# Motor1_PCIe.net
KiCad netlist of a schematic drawn in Altium Designer
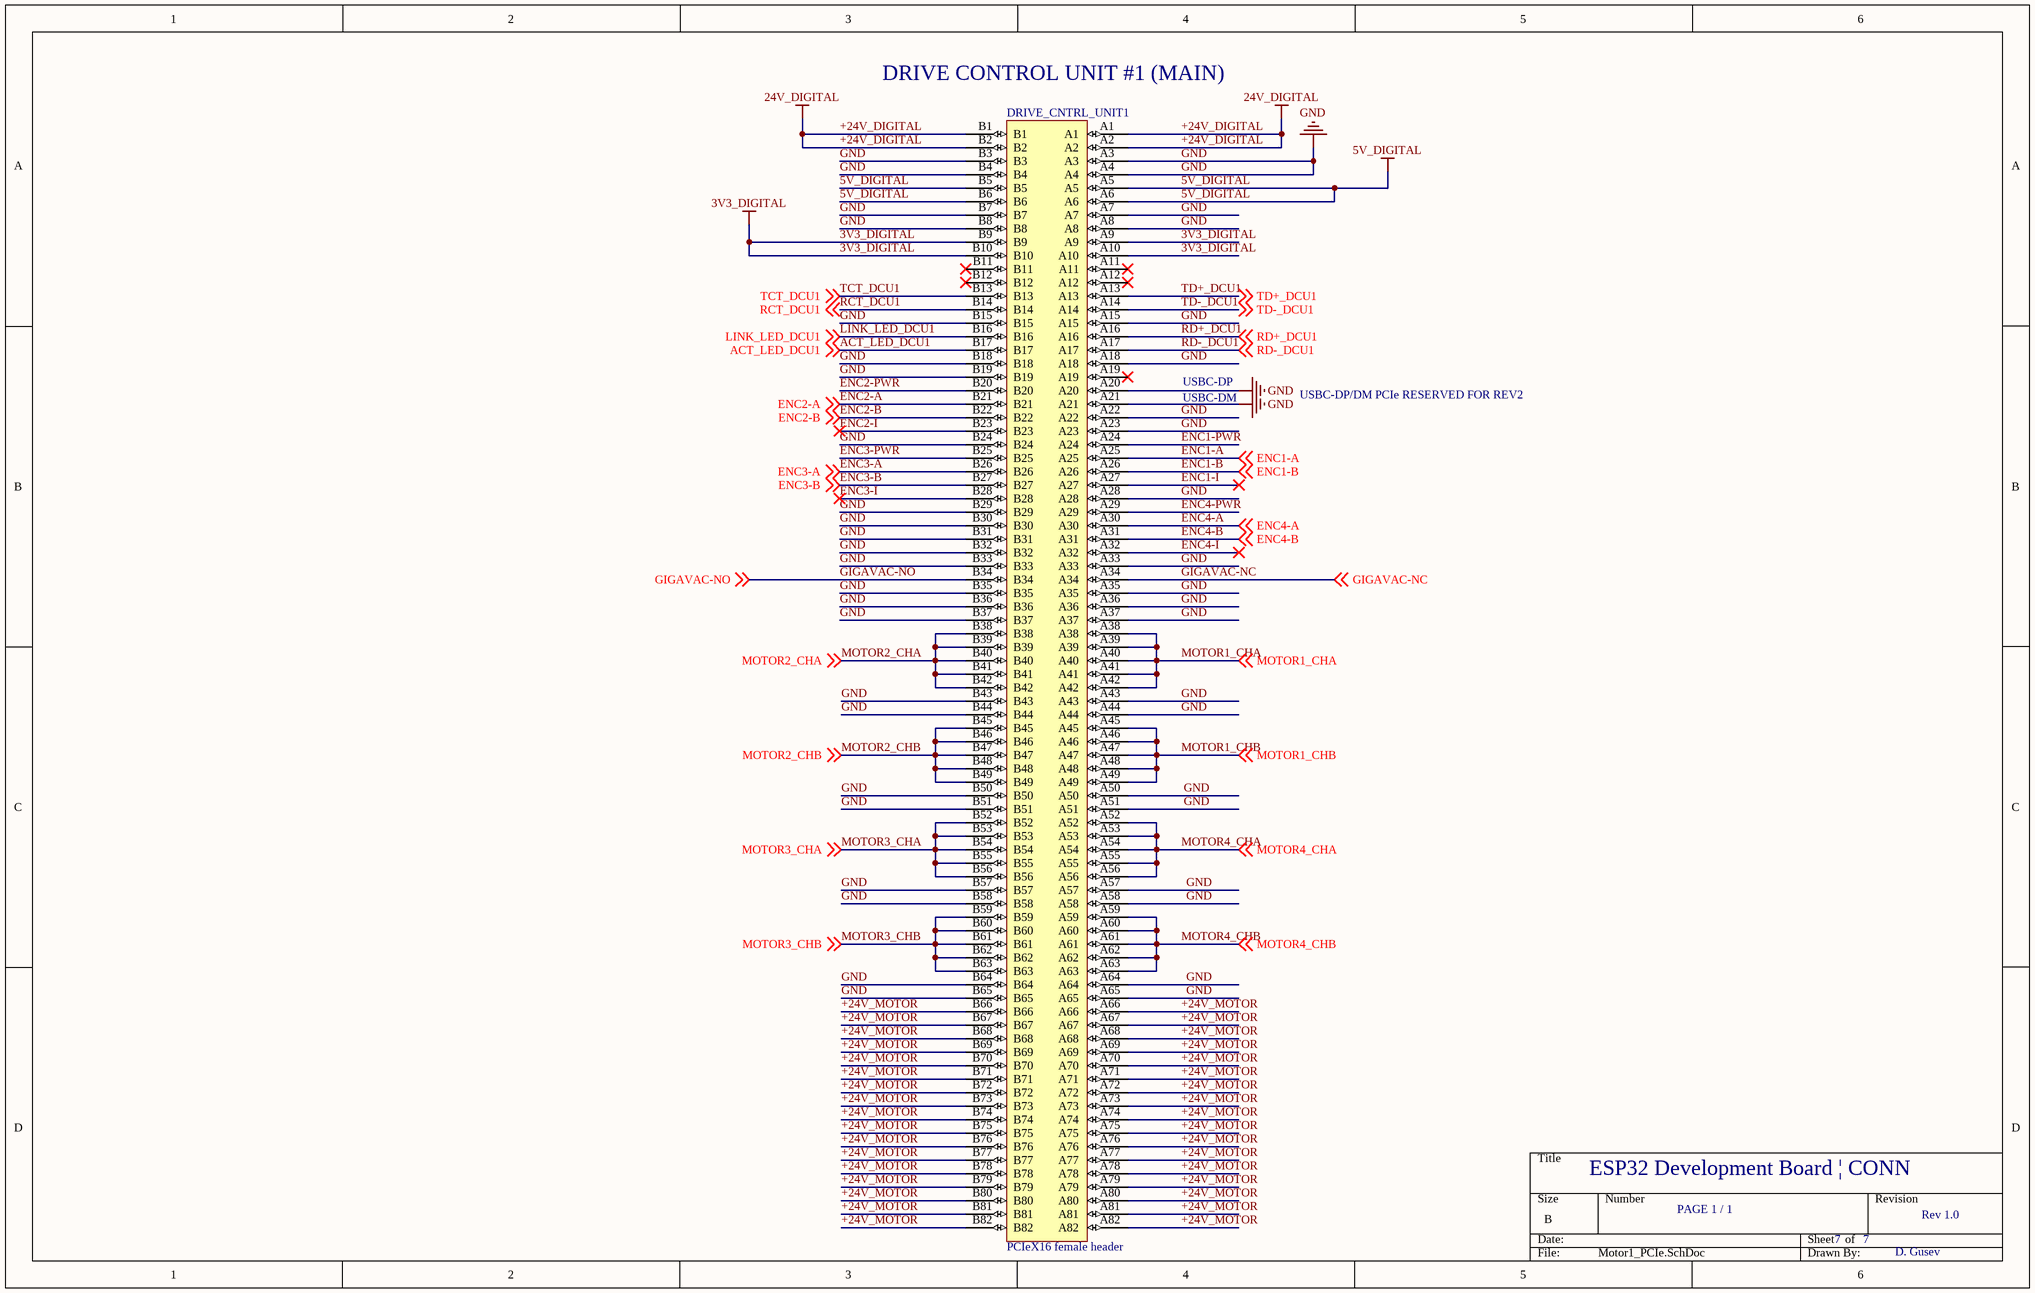
[diagram p0: Motor1_PCIe.SchDoc]

(export (version "E")
  (design (tool "Eeschema 10.0.6"))
  (components
    (comp (ref "DRIVE_CNTRL_UNIT1")
      (value "PCIeX16 female header")
      (footprint "SAMTEC_PCIE-164-02-X-D-TH")
      (description "164-position SAMTEC female header")
      (libsource (lib "ANTS-MotherBoard-B1") (part "PCIeX16 female header"))
    )
  )
  (nets
    (net (code "1") (name "/+24V_MOTOR") (class "Default")
      (node (ref "DRIVE_CNTRL_UNIT1") (pin "A66") (pinfunction "A66_A66") (pintype "bidirectional"))
      (node (ref "DRIVE_CNTRL_UNIT1") (pin "A67") (pinfunction "A67_A67") (pintype "bidirectional"))
      (node (ref "DRIVE_CNTRL_UNIT1") (pin "A68") (pinfunction "A68_A68") (pintype "bidirectional"))
      (node (ref "DRIVE_CNTRL_UNIT1") (pin "A69") (pinfunction "A69_A69") (pintype "bidirectional"))
      (node (ref "DRIVE_CNTRL_UNIT1") (pin "A70") (pinfunction "A70_A70") (pintype "bidirectional"))
      (node (ref "DRIVE_CNTRL_UNIT1") (pin "A71") (pinfunction "A71_A71") (pintype "bidirectional"))
      (node (ref "DRIVE_CNTRL_UNIT1") (pin "A72") (pinfunction "A72_A72") (pintype "bidirectional"))
      (node (ref "DRIVE_CNTRL_UNIT1") (pin "A73") (pinfunction "A73_A73") (pintype "bidirectional"))
      (node (ref "DRIVE_CNTRL_UNIT1") (pin "A74") (pinfunction "A74_A74") (pintype "bidirectional"))
      (node (ref "DRIVE_CNTRL_UNIT1") (pin "A75") (pinfunction "A75_A75") (pintype "bidirectional"))
      (node (ref "DRIVE_CNTRL_UNIT1") (pin "A76") (pinfunction "A76_A76") (pintype "bidirectional"))
      (node (ref "DRIVE_CNTRL_UNIT1") (pin "A77") (pinfunction "A77_A77") (pintype "bidirectional"))
      (node (ref "DRIVE_CNTRL_UNIT1") (pin "A78") (pinfunction "A78_A78") (pintype "bidirectional"))
      (node (ref "DRIVE_CNTRL_UNIT1") (pin "A79") (pinfunction "A79_A79") (pintype "bidirectional"))
      (node (ref "DRIVE_CNTRL_UNIT1") (pin "A80") (pinfunction "A80_A80") (pintype "bidirectional"))
      (node (ref "DRIVE_CNTRL_UNIT1") (pin "A81") (pinfunction "A81_A81") (pintype "bidirectional"))
      (node (ref "DRIVE_CNTRL_UNIT1") (pin "A82") (pinfunction "A82_A82") (pintype "bidirectional"))
      (node (ref "DRIVE_CNTRL_UNIT1") (pin "B66") (pinfunction "B66_B66") (pintype "bidirectional"))
      (node (ref "DRIVE_CNTRL_UNIT1") (pin "B67") (pinfunction "B67_B67") (pintype "bidirectional"))
      (node (ref "DRIVE_CNTRL_UNIT1") (pin "B68") (pinfunction "B68_B68") (pintype "bidirectional"))
      (node (ref "DRIVE_CNTRL_UNIT1") (pin "B69") (pinfunction "B69_B69") (pintype "bidirectional"))
      (node (ref "DRIVE_CNTRL_UNIT1") (pin "B70") (pinfunction "B70_B70") (pintype "bidirectional"))
      (node (ref "DRIVE_CNTRL_UNIT1") (pin "B71") (pinfunction "B71_B71") (pintype "bidirectional"))
      (node (ref "DRIVE_CNTRL_UNIT1") (pin "B72") (pinfunction "B72_B72") (pintype "bidirectional"))
      (node (ref "DRIVE_CNTRL_UNIT1") (pin "B73") (pinfunction "B73_B73") (pintype "bidirectional"))
      (node (ref "DRIVE_CNTRL_UNIT1") (pin "B74") (pinfunction "B74_B74") (pintype "bidirectional"))
      (node (ref "DRIVE_CNTRL_UNIT1") (pin "B75") (pinfunction "B75_B75") (pintype "bidirectional"))
      (node (ref "DRIVE_CNTRL_UNIT1") (pin "B76") (pinfunction "B76_B76") (pintype "bidirectional"))
      (node (ref "DRIVE_CNTRL_UNIT1") (pin "B77") (pinfunction "B77_B77") (pintype "bidirectional"))
      (node (ref "DRIVE_CNTRL_UNIT1") (pin "B78") (pinfunction "B78_B78") (pintype "bidirectional"))
      (node (ref "DRIVE_CNTRL_UNIT1") (pin "B79") (pinfunction "B79_B79") (pintype "bidirectional"))
      (node (ref "DRIVE_CNTRL_UNIT1") (pin "B80") (pinfunction "B80_B80") (pintype "bidirectional"))
      (node (ref "DRIVE_CNTRL_UNIT1") (pin "B81") (pinfunction "B81_B81") (pintype "bidirectional"))
      (node (ref "DRIVE_CNTRL_UNIT1") (pin "B82") (pinfunction "B82_B82") (pintype "bidirectional"))
    )
    (net (code "2") (name "/ENC1-I") (class "Default")
      (node (ref "DRIVE_CNTRL_UNIT1") (pin "A27") (pinfunction "A27_A27") (pintype "bidirectional+no_connect"))
    )
    (net (code "3") (name "/ENC1-PWR") (class "Default")
      (node (ref "DRIVE_CNTRL_UNIT1") (pin "A24") (pinfunction "A24_A24") (pintype "bidirectional"))
    )
    (net (code "4") (name "/ENC2-I") (class "Default")
      (node (ref "DRIVE_CNTRL_UNIT1") (pin "B23") (pinfunction "B23_B23") (pintype "bidirectional+no_connect"))
    )
    (net (code "5") (name "/ENC2-PWR") (class "Default")
      (node (ref "DRIVE_CNTRL_UNIT1") (pin "B20") (pinfunction "B20_B20") (pintype "bidirectional"))
    )
    (net (code "6") (name "/ENC3-I") (class "Default")
      (node (ref "DRIVE_CNTRL_UNIT1") (pin "B28") (pinfunction "B28_B28") (pintype "bidirectional+no_connect"))
    )
    (net (code "7") (name "/ENC3-PWR") (class "Default")
      (node (ref "DRIVE_CNTRL_UNIT1") (pin "B25") (pinfunction "B25_B25") (pintype "bidirectional"))
    )
    (net (code "8") (name "/ENC4-I") (class "Default")
      (node (ref "DRIVE_CNTRL_UNIT1") (pin "A32") (pinfunction "A32_A32") (pintype "bidirectional+no_connect"))
    )
    (net (code "9") (name "/ENC4-PWR") (class "Default")
      (node (ref "DRIVE_CNTRL_UNIT1") (pin "A29") (pinfunction "A29_A29") (pintype "bidirectional"))
    )
    (net (code "10") (name "3V3_DIGITAL") (class "Default")
      (node (ref "DRIVE_CNTRL_UNIT1") (pin "A10") (pinfunction "A10_A10") (pintype "bidirectional"))
      (node (ref "DRIVE_CNTRL_UNIT1") (pin "A9") (pinfunction "A9_A9") (pintype "bidirectional"))
      (node (ref "DRIVE_CNTRL_UNIT1") (pin "B10") (pinfunction "B10_B10") (pintype "bidirectional"))
      (node (ref "DRIVE_CNTRL_UNIT1") (pin "B9") (pinfunction "B9_B9") (pintype "bidirectional"))
    )
    (net (code "11") (name "5V_DIGITAL") (class "Default")
      (node (ref "DRIVE_CNTRL_UNIT1") (pin "A5") (pinfunction "A5_A5") (pintype "bidirectional"))
      (node (ref "DRIVE_CNTRL_UNIT1") (pin "A6") (pinfunction "A6_A6") (pintype "bidirectional"))
      (node (ref "DRIVE_CNTRL_UNIT1") (pin "B5") (pinfunction "B5_B5") (pintype "bidirectional"))
      (node (ref "DRIVE_CNTRL_UNIT1") (pin "B6") (pinfunction "B6_B6") (pintype "bidirectional"))
    )
    (net (code "12") (name "24V_DIGITAL") (class "Default")
      (node (ref "DRIVE_CNTRL_UNIT1") (pin "A1") (pinfunction "A1_A1") (pintype "bidirectional"))
      (node (ref "DRIVE_CNTRL_UNIT1") (pin "A2") (pinfunction "A2_A2") (pintype "bidirectional"))
      (node (ref "DRIVE_CNTRL_UNIT1") (pin "B1") (pinfunction "B1_B1") (pintype "bidirectional"))
      (node (ref "DRIVE_CNTRL_UNIT1") (pin "B2") (pinfunction "B2_B2") (pintype "bidirectional"))
    )
    (net (code "13") (name "ACT_LED_DCU1") (class "Default")
      (node (ref "DRIVE_CNTRL_UNIT1") (pin "B17") (pinfunction "B17_B17") (pintype "bidirectional"))
    )
    (net (code "14") (name "ENC1-A") (class "Default")
      (node (ref "DRIVE_CNTRL_UNIT1") (pin "A25") (pinfunction "A25_A25") (pintype "bidirectional"))
    )
    (net (code "15") (name "ENC1-B") (class "Default")
      (node (ref "DRIVE_CNTRL_UNIT1") (pin "A26") (pinfunction "A26_A26") (pintype "bidirectional"))
    )
    (net (code "16") (name "ENC2-A") (class "Default")
      (node (ref "DRIVE_CNTRL_UNIT1") (pin "B21") (pinfunction "B21_B21") (pintype "bidirectional"))
    )
    (net (code "17") (name "ENC2-B") (class "Default")
      (node (ref "DRIVE_CNTRL_UNIT1") (pin "B22") (pinfunction "B22_B22") (pintype "bidirectional"))
    )
    (net (code "18") (name "ENC3-A") (class "Default")
      (node (ref "DRIVE_CNTRL_UNIT1") (pin "B26") (pinfunction "B26_B26") (pintype "bidirectional"))
    )
    (net (code "19") (name "ENC3-B") (class "Default")
      (node (ref "DRIVE_CNTRL_UNIT1") (pin "B27") (pinfunction "B27_B27") (pintype "bidirectional"))
    )
    (net (code "20") (name "ENC4-A") (class "Default")
      (node (ref "DRIVE_CNTRL_UNIT1") (pin "A30") (pinfunction "A30_A30") (pintype "bidirectional"))
    )
    (net (code "21") (name "ENC4-B") (class "Default")
      (node (ref "DRIVE_CNTRL_UNIT1") (pin "A31") (pinfunction "A31_A31") (pintype "bidirectional"))
    )
    (net (code "22") (name "GIGAVAC-NC") (class "Default")
      (node (ref "DRIVE_CNTRL_UNIT1") (pin "A34") (pinfunction "A34_A34") (pintype "bidirectional"))
    )
    (net (code "23") (name "GIGAVAC-NO") (class "Default")
      (node (ref "DRIVE_CNTRL_UNIT1") (pin "B34") (pinfunction "B34_B34") (pintype "bidirectional"))
    )
    (net (code "24") (name "GND") (class "Default")
      (node (ref "DRIVE_CNTRL_UNIT1") (pin "A15") (pinfunction "A15_A15") (pintype "bidirectional"))
      (node (ref "DRIVE_CNTRL_UNIT1") (pin "A18") (pinfunction "A18_A18") (pintype "bidirectional"))
      (node (ref "DRIVE_CNTRL_UNIT1") (pin "A20") (pinfunction "A20_A20") (pintype "bidirectional"))
      (node (ref "DRIVE_CNTRL_UNIT1") (pin "A21") (pinfunction "A21_A21") (pintype "bidirectional"))
      (node (ref "DRIVE_CNTRL_UNIT1") (pin "A22") (pinfunction "A22_A22") (pintype "bidirectional"))
      (node (ref "DRIVE_CNTRL_UNIT1") (pin "A23") (pinfunction "A23_A23") (pintype "bidirectional"))
      (node (ref "DRIVE_CNTRL_UNIT1") (pin "A28") (pinfunction "A28_A28") (pintype "bidirectional"))
      (node (ref "DRIVE_CNTRL_UNIT1") (pin "A3") (pinfunction "A3_A3") (pintype "bidirectional"))
      (node (ref "DRIVE_CNTRL_UNIT1") (pin "A33") (pinfunction "A33_A33") (pintype "bidirectional"))
      (node (ref "DRIVE_CNTRL_UNIT1") (pin "A35") (pinfunction "A35_A35") (pintype "bidirectional"))
      (node (ref "DRIVE_CNTRL_UNIT1") (pin "A36") (pinfunction "A36_A36") (pintype "bidirectional"))
      (node (ref "DRIVE_CNTRL_UNIT1") (pin "A37") (pinfunction "A37_A37") (pintype "bidirectional"))
      (node (ref "DRIVE_CNTRL_UNIT1") (pin "A4") (pinfunction "A4_A4") (pintype "bidirectional"))
      (node (ref "DRIVE_CNTRL_UNIT1") (pin "A43") (pinfunction "A43_A43") (pintype "bidirectional"))
      (node (ref "DRIVE_CNTRL_UNIT1") (pin "A44") (pinfunction "A44_A44") (pintype "bidirectional"))
      (node (ref "DRIVE_CNTRL_UNIT1") (pin "A50") (pinfunction "A50_A50") (pintype "bidirectional"))
      (node (ref "DRIVE_CNTRL_UNIT1") (pin "A51") (pinfunction "A51_A51") (pintype "bidirectional"))
      (node (ref "DRIVE_CNTRL_UNIT1") (pin "A57") (pinfunction "A57_A57") (pintype "bidirectional"))
      (node (ref "DRIVE_CNTRL_UNIT1") (pin "A58") (pinfunction "A58_A58") (pintype "bidirectional"))
      (node (ref "DRIVE_CNTRL_UNIT1") (pin "A64") (pinfunction "A64_A64") (pintype "bidirectional"))
      (node (ref "DRIVE_CNTRL_UNIT1") (pin "A65") (pinfunction "A65_A65") (pintype "bidirectional"))
      (node (ref "DRIVE_CNTRL_UNIT1") (pin "A7") (pinfunction "A7_A7") (pintype "bidirectional"))
      (node (ref "DRIVE_CNTRL_UNIT1") (pin "A8") (pinfunction "A8_A8") (pintype "bidirectional"))
      (node (ref "DRIVE_CNTRL_UNIT1") (pin "B15") (pinfunction "B15_B15") (pintype "bidirectional"))
      (node (ref "DRIVE_CNTRL_UNIT1") (pin "B18") (pinfunction "B18_B18") (pintype "bidirectional"))
      (node (ref "DRIVE_CNTRL_UNIT1") (pin "B19") (pinfunction "B19_B19") (pintype "bidirectional"))
      (node (ref "DRIVE_CNTRL_UNIT1") (pin "B24") (pinfunction "B24_B24") (pintype "bidirectional"))
      (node (ref "DRIVE_CNTRL_UNIT1") (pin "B29") (pinfunction "B29_B29") (pintype "bidirectional"))
      (node (ref "DRIVE_CNTRL_UNIT1") (pin "B3") (pinfunction "B3_B3") (pintype "bidirectional"))
      (node (ref "DRIVE_CNTRL_UNIT1") (pin "B30") (pinfunction "B30_B30") (pintype "bidirectional"))
      (node (ref "DRIVE_CNTRL_UNIT1") (pin "B31") (pinfunction "B31_B31") (pintype "bidirectional"))
      (node (ref "DRIVE_CNTRL_UNIT1") (pin "B32") (pinfunction "B32_B32") (pintype "bidirectional"))
      (node (ref "DRIVE_CNTRL_UNIT1") (pin "B33") (pinfunction "B33_B33") (pintype "bidirectional"))
      (node (ref "DRIVE_CNTRL_UNIT1") (pin "B35") (pinfunction "B35_B35") (pintype "bidirectional"))
      (node (ref "DRIVE_CNTRL_UNIT1") (pin "B36") (pinfunction "B36_B36") (pintype "bidirectional"))
      (node (ref "DRIVE_CNTRL_UNIT1") (pin "B37") (pinfunction "B37_B37") (pintype "bidirectional"))
      (node (ref "DRIVE_CNTRL_UNIT1") (pin "B4") (pinfunction "B4_B4") (pintype "bidirectional"))
      (node (ref "DRIVE_CNTRL_UNIT1") (pin "B43") (pinfunction "B43_B43") (pintype "bidirectional"))
      (node (ref "DRIVE_CNTRL_UNIT1") (pin "B44") (pinfunction "B44_B44") (pintype "bidirectional"))
      (node (ref "DRIVE_CNTRL_UNIT1") (pin "B50") (pinfunction "B50_B50") (pintype "bidirectional"))
      (node (ref "DRIVE_CNTRL_UNIT1") (pin "B51") (pinfunction "B51_B51") (pintype "bidirectional"))
      (node (ref "DRIVE_CNTRL_UNIT1") (pin "B57") (pinfunction "B57_B57") (pintype "bidirectional"))
      (node (ref "DRIVE_CNTRL_UNIT1") (pin "B58") (pinfunction "B58_B58") (pintype "bidirectional"))
      (node (ref "DRIVE_CNTRL_UNIT1") (pin "B64") (pinfunction "B64_B64") (pintype "bidirectional"))
      (node (ref "DRIVE_CNTRL_UNIT1") (pin "B65") (pinfunction "B65_B65") (pintype "bidirectional"))
      (node (ref "DRIVE_CNTRL_UNIT1") (pin "B7") (pinfunction "B7_B7") (pintype "bidirectional"))
      (node (ref "DRIVE_CNTRL_UNIT1") (pin "B8") (pinfunction "B8_B8") (pintype "bidirectional"))
    )
    (net (code "25") (name "LINK_LED_DCU1") (class "Default")
      (node (ref "DRIVE_CNTRL_UNIT1") (pin "B16") (pinfunction "B16_B16") (pintype "bidirectional"))
    )
    (net (code "26") (name "MOTOR1_CHA") (class "Default")
      (node (ref "DRIVE_CNTRL_UNIT1") (pin "A38") (pinfunction "A38_A38") (pintype "bidirectional"))
      (node (ref "DRIVE_CNTRL_UNIT1") (pin "A39") (pinfunction "A39_A39") (pintype "bidirectional"))
      (node (ref "DRIVE_CNTRL_UNIT1") (pin "A40") (pinfunction "A40_A40") (pintype "bidirectional"))
      (node (ref "DRIVE_CNTRL_UNIT1") (pin "A41") (pinfunction "A41_A41") (pintype "bidirectional"))
      (node (ref "DRIVE_CNTRL_UNIT1") (pin "A42") (pinfunction "A42_A42") (pintype "bidirectional"))
    )
    (net (code "27") (name "MOTOR1_CHB") (class "Default")
      (node (ref "DRIVE_CNTRL_UNIT1") (pin "A45") (pinfunction "A45_A45") (pintype "bidirectional"))
      (node (ref "DRIVE_CNTRL_UNIT1") (pin "A46") (pinfunction "A46_A46") (pintype "bidirectional"))
      (node (ref "DRIVE_CNTRL_UNIT1") (pin "A47") (pinfunction "A47_A47") (pintype "bidirectional"))
      (node (ref "DRIVE_CNTRL_UNIT1") (pin "A48") (pinfunction "A48_A48") (pintype "bidirectional"))
      (node (ref "DRIVE_CNTRL_UNIT1") (pin "A49") (pinfunction "A49_A49") (pintype "bidirectional"))
    )
    (net (code "28") (name "MOTOR2_CHA") (class "Default")
      (node (ref "DRIVE_CNTRL_UNIT1") (pin "B38") (pinfunction "B38_B38") (pintype "bidirectional"))
      (node (ref "DRIVE_CNTRL_UNIT1") (pin "B39") (pinfunction "B39_B39") (pintype "bidirectional"))
      (node (ref "DRIVE_CNTRL_UNIT1") (pin "B40") (pinfunction "B40_B40") (pintype "bidirectional"))
      (node (ref "DRIVE_CNTRL_UNIT1") (pin "B41") (pinfunction "B41_B41") (pintype "bidirectional"))
      (node (ref "DRIVE_CNTRL_UNIT1") (pin "B42") (pinfunction "B42_B42") (pintype "bidirectional"))
    )
    (net (code "29") (name "MOTOR2_CHB") (class "Default")
      (node (ref "DRIVE_CNTRL_UNIT1") (pin "B45") (pinfunction "B45_B45") (pintype "bidirectional"))
      (node (ref "DRIVE_CNTRL_UNIT1") (pin "B46") (pinfunction "B46_B46") (pintype "bidirectional"))
      (node (ref "DRIVE_CNTRL_UNIT1") (pin "B47") (pinfunction "B47_B47") (pintype "bidirectional"))
      (node (ref "DRIVE_CNTRL_UNIT1") (pin "B48") (pinfunction "B48_B48") (pintype "bidirectional"))
      (node (ref "DRIVE_CNTRL_UNIT1") (pin "B49") (pinfunction "B49_B49") (pintype "bidirectional"))
    )
    (net (code "30") (name "MOTOR3_CHA") (class "Default")
      (node (ref "DRIVE_CNTRL_UNIT1") (pin "B52") (pinfunction "B52_B52") (pintype "bidirectional"))
      (node (ref "DRIVE_CNTRL_UNIT1") (pin "B53") (pinfunction "B53_B53") (pintype "bidirectional"))
      (node (ref "DRIVE_CNTRL_UNIT1") (pin "B54") (pinfunction "B54_B54") (pintype "bidirectional"))
      (node (ref "DRIVE_CNTRL_UNIT1") (pin "B55") (pinfunction "B55_B55") (pintype "bidirectional"))
      (node (ref "DRIVE_CNTRL_UNIT1") (pin "B56") (pinfunction "B56_B56") (pintype "bidirectional"))
    )
    (net (code "31") (name "MOTOR3_CHB") (class "Default")
      (node (ref "DRIVE_CNTRL_UNIT1") (pin "B59") (pinfunction "B59_B59") (pintype "bidirectional"))
      (node (ref "DRIVE_CNTRL_UNIT1") (pin "B60") (pinfunction "B60_B60") (pintype "bidirectional"))
      (node (ref "DRIVE_CNTRL_UNIT1") (pin "B61") (pinfunction "B61_B61") (pintype "bidirectional"))
      (node (ref "DRIVE_CNTRL_UNIT1") (pin "B62") (pinfunction "B62_B62") (pintype "bidirectional"))
      (node (ref "DRIVE_CNTRL_UNIT1") (pin "B63") (pinfunction "B63_B63") (pintype "bidirectional"))
    )
    (net (code "32") (name "MOTOR4_CHA") (class "Default")
      (node (ref "DRIVE_CNTRL_UNIT1") (pin "A52") (pinfunction "A52_A52") (pintype "bidirectional"))
      (node (ref "DRIVE_CNTRL_UNIT1") (pin "A53") (pinfunction "A53_A53") (pintype "bidirectional"))
      (node (ref "DRIVE_CNTRL_UNIT1") (pin "A54") (pinfunction "A54_A54") (pintype "bidirectional"))
      (node (ref "DRIVE_CNTRL_UNIT1") (pin "A55") (pinfunction "A55_A55") (pintype "bidirectional"))
      (node (ref "DRIVE_CNTRL_UNIT1") (pin "A56") (pinfunction "A56_A56") (pintype "bidirectional"))
    )
    (net (code "33") (name "MOTOR4_CHB") (class "Default")
      (node (ref "DRIVE_CNTRL_UNIT1") (pin "A59") (pinfunction "A59_A59") (pintype "bidirectional"))
      (node (ref "DRIVE_CNTRL_UNIT1") (pin "A60") (pinfunction "A60_A60") (pintype "bidirectional"))
      (node (ref "DRIVE_CNTRL_UNIT1") (pin "A61") (pinfunction "A61_A61") (pintype "bidirectional"))
      (node (ref "DRIVE_CNTRL_UNIT1") (pin "A62") (pinfunction "A62_A62") (pintype "bidirectional"))
      (node (ref "DRIVE_CNTRL_UNIT1") (pin "A63") (pinfunction "A63_A63") (pintype "bidirectional"))
    )
    (net (code "34") (name "RCT_DCU1") (class "Default")
      (node (ref "DRIVE_CNTRL_UNIT1") (pin "B14") (pinfunction "B14_B14") (pintype "bidirectional"))
    )
    (net (code "35") (name "RD+_DCU1") (class "Default")
      (node (ref "DRIVE_CNTRL_UNIT1") (pin "A16") (pinfunction "A16_A16") (pintype "bidirectional"))
    )
    (net (code "36") (name "RD-_DCU1") (class "Default")
      (node (ref "DRIVE_CNTRL_UNIT1") (pin "A17") (pinfunction "A17_A17") (pintype "bidirectional"))
    )
    (net (code "37") (name "TCT_DCU1") (class "Default")
      (node (ref "DRIVE_CNTRL_UNIT1") (pin "B13") (pinfunction "B13_B13") (pintype "bidirectional"))
    )
    (net (code "38") (name "TD+_DCU1") (class "Default")
      (node (ref "DRIVE_CNTRL_UNIT1") (pin "A13") (pinfunction "A13_A13") (pintype "bidirectional"))
    )
    (net (code "39") (name "TD-_DCU1") (class "Default")
      (node (ref "DRIVE_CNTRL_UNIT1") (pin "A14") (pinfunction "A14_A14") (pintype "bidirectional"))
    )
    (net (code "40") (name "unconnected-(DRIVE_CNTRL_UNIT1-PadA11)") (class "Default")
      (node (ref "DRIVE_CNTRL_UNIT1") (pin "A11") (pinfunction "A11_A11") (pintype "bidirectional+no_connect"))
    )
    (net (code "41") (name "unconnected-(DRIVE_CNTRL_UNIT1-PadA12)") (class "Default")
      (node (ref "DRIVE_CNTRL_UNIT1") (pin "A12") (pinfunction "A12_A12") (pintype "bidirectional+no_connect"))
    )
    (net (code "42") (name "unconnected-(DRIVE_CNTRL_UNIT1-PadA19)") (class "Default")
      (node (ref "DRIVE_CNTRL_UNIT1") (pin "A19") (pinfunction "A19_A19") (pintype "bidirectional+no_connect"))
    )
    (net (code "43") (name "unconnected-(DRIVE_CNTRL_UNIT1-PadB11)") (class "Default")
      (node (ref "DRIVE_CNTRL_UNIT1") (pin "B11") (pinfunction "B11_B11") (pintype "bidirectional+no_connect"))
    )
    (net (code "44") (name "unconnected-(DRIVE_CNTRL_UNIT1-PadB12)") (class "Default")
      (node (ref "DRIVE_CNTRL_UNIT1") (pin "B12") (pinfunction "B12_B12") (pintype "bidirectional+no_connect"))
    )
  )
)
